# 32-041.net
KiCad netlist of a schematic drawn in Altium Designer
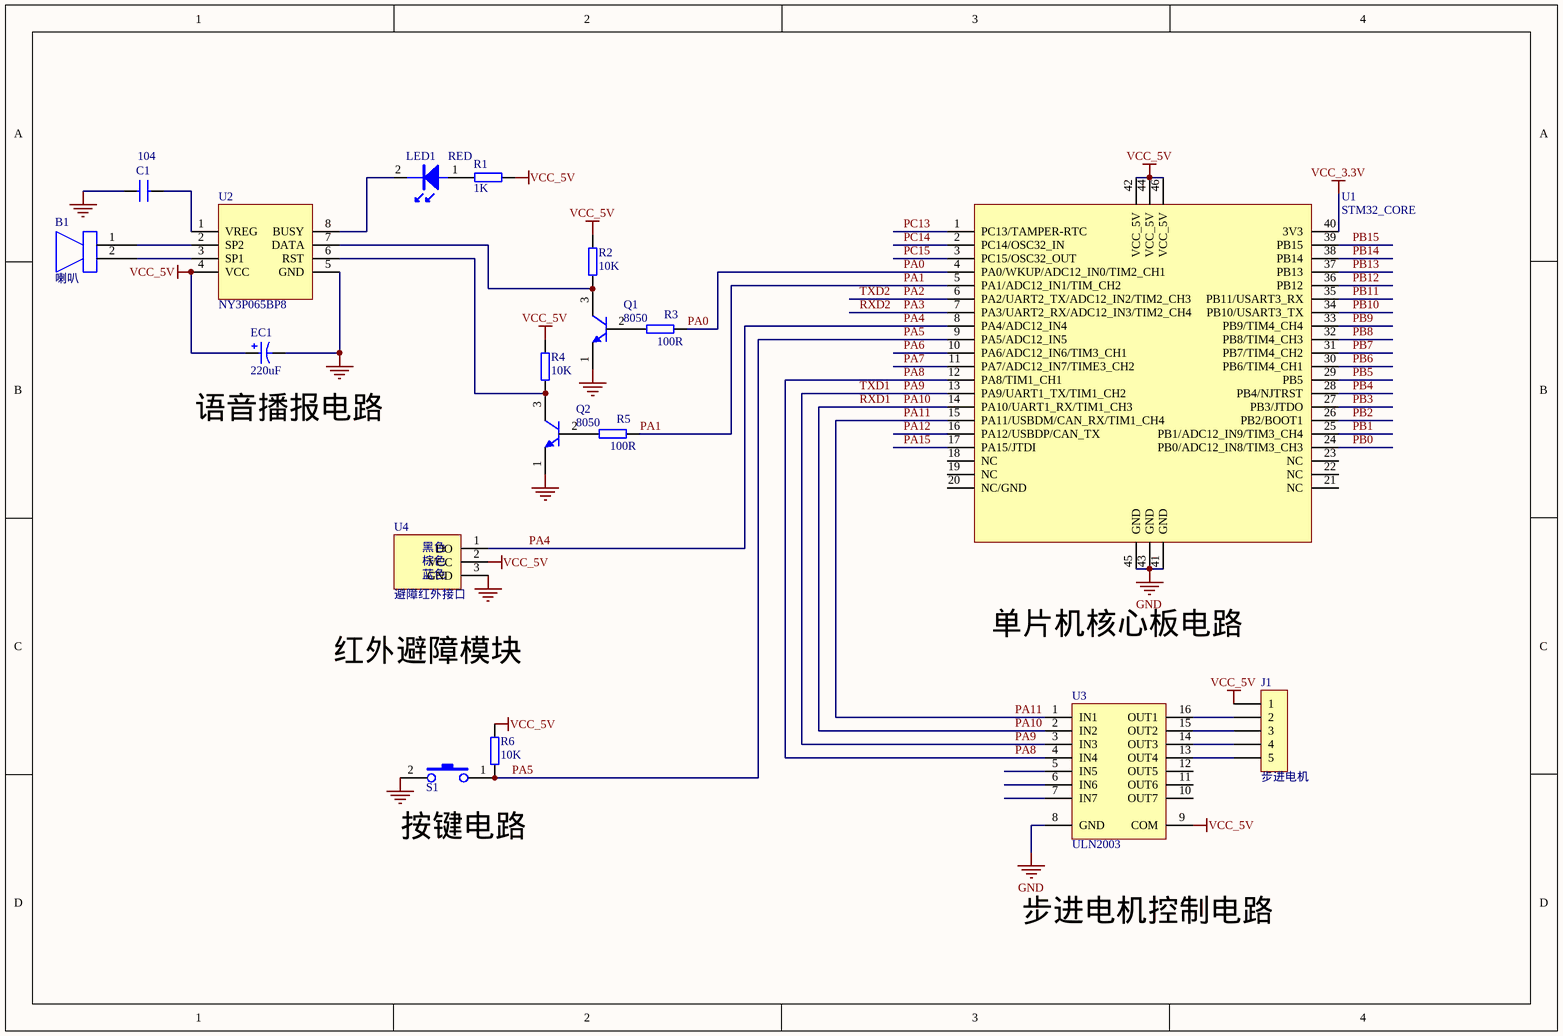
[diagram p0: 32-041原理图（源文件格式）.SchDoc]

(export (version "E")
  (design (tool "Eeschema 10.0.6"))
  (components
    (comp (ref "B1") (value "喇叭") (footprint "喇叭") (libsource (lib "参考") (part "喇叭")))
    (comp (ref "C1")
      (value "104")
      (footprint "RAD-0.1")
      (description "无极性电容")
      (libsource (lib "参考") (part "CAP"))
    )
    (comp (ref "EC1")
      (value "220uF")
      (footprint "RB.15/.3")
      (description "极性电容")
      (libsource (lib "参考") (part "CAP_EC"))
    )
    (comp (ref "J1")
      (value "步进电机")
      (footprint "SIP5-2.54")
      (description "步进电机接口")
      (libsource (lib "参考") (part "步进电机"))
    )
    (comp (ref "LED1")
      (value "RED")
      (footprint "LED_D3MM12")
      (description "LED灯")
      (libsource (lib "参考") (part "LED12"))
    )
    (comp (ref "Q1")
      (value "8050")
      (footprint "TO-92")
      (description "三极管")
      (libsource (lib "参考") (part "9013"))
    )
    (comp (ref "Q2")
      (value "8050")
      (footprint "TO-92")
      (description "三极管")
      (libsource (lib "参考") (part "9013"))
    )
    (comp (ref "R1")
      (value "1K")
      (footprint "AXIAL0.3")
      (description "电阻")
      (libsource (lib "参考") (part "RES"))
    )
    (comp (ref "R2")
      (value "10K")
      (footprint "AXIAL0.3")
      (description "电阻")
      (libsource (lib "参考") (part "RES"))
    )
    (comp (ref "R3")
      (value "100R")
      (footprint "AXIAL0.3")
      (description "电阻")
      (libsource (lib "参考") (part "RES"))
    )
    (comp (ref "R4")
      (value "10K")
      (footprint "AXIAL0.3")
      (description "电阻")
      (libsource (lib "参考") (part "RES"))
    )
    (comp (ref "R5")
      (value "100R")
      (footprint "AXIAL0.3")
      (description "电阻")
      (libsource (lib "参考") (part "RES"))
    )
    (comp (ref "R6")
      (value "10K")
      (footprint "AXIAL0.3")
      (description "电阻")
      (libsource (lib "参考") (part "RES"))
    )
    (comp (ref "S1")
      (value "BUTTOM")
      (footprint "BUTTOM_6x6DIP")
      (description "按键")
      (libsource (lib "参考") (part "BUTTOM"))
    )
    (comp (ref "U1")
      (value "STM32_CORE")
      (footprint "STM32_CORE")
      (description "STM32核心板")
      (libsource (lib "参考") (part "STM32_CORE"))
    )
    (comp (ref "U2")
      (value "NY3P065BP8")
      (footprint "DIP8")
      (description "语音芯片")
      (libsource (lib "参考") (part "NY3P065BP8"))
    )
    (comp (ref "U3")
      (value "ULN2003")
      (footprint "DIP16")
      (description "ULN2003芯片")
      (libsource (lib "参考") (part "ULN2003A"))
    )
    (comp (ref "U4")
      (value "避障红外接口")
      (footprint "红外接口")
      (description "避障红外探头模块")
      (libsource (lib "参考") (part "避障红外接口"))
    )
  )
  (nets
    (net (code "1") (name "/PA0") (class "Default")
      (node (ref "R3") (pin "1") (pinfunction "1_1") (pintype "passive"))
      (node (ref "U1") (pin "4") (pinfunction "PA0/WKUP/ADC12_IN0/TIM2_CH1_4") (pintype "passive"))
    )
    (net (code "2") (name "/PA1") (class "Default")
      (node (ref "R5") (pin "1") (pinfunction "1_1") (pintype "passive"))
      (node (ref "U1") (pin "5") (pinfunction "PA1/ADC12_IN1/TIM_CH2_5") (pintype "passive"))
    )
    (net (code "3") (name "/PA2") (class "Default")
      (node (ref "U1") (pin "6") (pinfunction "PA2/UART2_TX/ADC12_IN2/TIM2_CH3_6") (pintype "passive"))
    )
    (net (code "4") (name "/PA3") (class "Default")
      (node (ref "U1") (pin "7") (pinfunction "PA3/UART2_RX/ADC12_IN3/TIM2_CH4_7") (pintype "passive"))
    )
    (net (code "5") (name "/PA4") (class "Default")
      (node (ref "U1") (pin "8") (pinfunction "PA4/ADC12_IN4_8") (pintype "passive"))
      (node (ref "U4") (pin "1") (pinfunction "DO_1") (pintype "passive"))
    )
    (net (code "6") (name "/PA5") (class "Default")
      (node (ref "R6") (pin "1") (pinfunction "1_1") (pintype "passive"))
      (node (ref "S1") (pin "1") (pinfunction "1_1") (pintype "passive"))
      (node (ref "U1") (pin "9") (pinfunction "PA5/ADC12_IN5_9") (pintype "passive"))
    )
    (net (code "7") (name "/PA6") (class "Default")
      (node (ref "U1") (pin "10") (pinfunction "PA6/ADC12_IN6/TIM3_CH1_10") (pintype "passive"))
    )
    (net (code "8") (name "/PA7") (class "Default")
      (node (ref "U1") (pin "11") (pinfunction "PA7/ADC12_IN7/TIME3_CH2_11") (pintype "passive"))
    )
    (net (code "9") (name "/PA8") (class "Default")
      (node (ref "U1") (pin "12") (pinfunction "PA8/TIM1_CH1_12") (pintype "passive"))
      (node (ref "U3") (pin "4") (pinfunction "IN4_4") (pintype "passive"))
    )
    (net (code "10") (name "/PA9") (class "Default")
      (node (ref "U1") (pin "13") (pinfunction "PA9/UART1_TX/TIM1_CH2_13") (pintype "passive"))
      (node (ref "U3") (pin "3") (pinfunction "IN3_3") (pintype "passive"))
    )
    (net (code "11") (name "/PA10") (class "Default")
      (node (ref "U1") (pin "14") (pinfunction "PA10/UART1_RX/TIM1_CH3_14") (pintype "passive"))
      (node (ref "U3") (pin "2") (pinfunction "IN2_2") (pintype "passive"))
    )
    (net (code "12") (name "/PA11") (class "Default")
      (node (ref "U1") (pin "15") (pinfunction "PA11/USBDM/CAN_RX/TIM1_CH4_15") (pintype "passive"))
      (node (ref "U3") (pin "1") (pinfunction "IN1_1") (pintype "passive"))
    )
    (net (code "13") (name "/PA12") (class "Default")
      (node (ref "U1") (pin "16") (pinfunction "PA12/USBDP/CAN_TX_16") (pintype "passive"))
    )
    (net (code "14") (name "/PA15") (class "Default")
      (node (ref "U1") (pin "17") (pinfunction "PA15/JTDI_17") (pintype "passive"))
    )
    (net (code "15") (name "/PB0") (class "Default")
      (node (ref "U1") (pin "24") (pinfunction "PB0/ADC12_IN8/TIM3_CH3_24") (pintype "passive"))
    )
    (net (code "16") (name "/PB1") (class "Default")
      (node (ref "U1") (pin "25") (pinfunction "PB1/ADC12_IN9/TIM3_CH4_25") (pintype "passive"))
    )
    (net (code "17") (name "/PB2") (class "Default")
      (node (ref "U1") (pin "26") (pinfunction "PB2/BOOT1_26") (pintype "passive"))
    )
    (net (code "18") (name "/PB3") (class "Default")
      (node (ref "U1") (pin "27") (pinfunction "PB3/JTDO_27") (pintype "passive"))
    )
    (net (code "19") (name "/PB4") (class "Default")
      (node (ref "U1") (pin "28") (pinfunction "PB4/NJTRST_28") (pintype "passive"))
    )
    (net (code "20") (name "/PB5") (class "Default")
      (node (ref "U1") (pin "29") (pinfunction "PB5_29") (pintype "passive"))
    )
    (net (code "21") (name "/PB6") (class "Default")
      (node (ref "U1") (pin "30") (pinfunction "PB6/TIM4_CH1_30") (pintype "passive"))
    )
    (net (code "22") (name "/PB7") (class "Default")
      (node (ref "U1") (pin "31") (pinfunction "PB7/TIM4_CH2_31") (pintype "passive"))
    )
    (net (code "23") (name "/PB8") (class "Default")
      (node (ref "U1") (pin "32") (pinfunction "PB8/TIM4_CH3_32") (pintype "passive"))
    )
    (net (code "24") (name "/PB9") (class "Default")
      (node (ref "U1") (pin "33") (pinfunction "PB9/TIM4_CH4_33") (pintype "passive"))
    )
    (net (code "25") (name "/PB10") (class "Default")
      (node (ref "U1") (pin "34") (pinfunction "PB10/USART3_TX_34") (pintype "passive"))
    )
    (net (code "26") (name "/PB11") (class "Default")
      (node (ref "U1") (pin "35") (pinfunction "PB11/USART3_RX_35") (pintype "passive"))
    )
    (net (code "27") (name "/PB12") (class "Default")
      (node (ref "U1") (pin "36") (pinfunction "PB12_36") (pintype "passive"))
    )
    (net (code "28") (name "/PB13") (class "Default")
      (node (ref "U1") (pin "37") (pinfunction "PB13_37") (pintype "passive"))
    )
    (net (code "29") (name "/PB14") (class "Default")
      (node (ref "U1") (pin "38") (pinfunction "PB14_38") (pintype "passive"))
    )
    (net (code "30") (name "/PB15") (class "Default")
      (node (ref "U1") (pin "39") (pinfunction "PB15_39") (pintype "passive"))
    )
    (net (code "31") (name "/PC13") (class "Default")
      (node (ref "U1") (pin "1") (pinfunction "PC13/TAMPER-RTC_1") (pintype "passive"))
    )
    (net (code "32") (name "/PC14") (class "Default")
      (node (ref "U1") (pin "2") (pinfunction "PC14/OSC32_IN_2") (pintype "passive"))
    )
    (net (code "33") (name "/PC15") (class "Default")
      (node (ref "U1") (pin "3") (pinfunction "PC15/OSC32_OUT_3") (pintype "passive"))
    )
    (net (code "34") (name "GND") (class "Default")
      (node (ref "C1") (pin "1") (pinfunction "1_1") (pintype "passive"))
      (node (ref "EC1") (pin "2") (pinfunction "2_2") (pintype "passive"))
      (node (ref "Q1") (pin "1") (pinfunction "1_1") (pintype "passive"))
      (node (ref "Q2") (pin "1") (pinfunction "1_1") (pintype "passive"))
      (node (ref "S1") (pin "2") (pinfunction "2_2") (pintype "passive"))
      (node (ref "U1") (pin "41") (pinfunction "GND_41") (pintype "passive"))
      (node (ref "U1") (pin "43") (pinfunction "GND_43") (pintype "passive"))
      (node (ref "U1") (pin "45") (pinfunction "GND_45") (pintype "passive"))
      (node (ref "U2") (pin "5") (pinfunction "GND_5") (pintype "passive"))
      (node (ref "U3") (pin "8") (pinfunction "GND_8") (pintype "passive"))
      (node (ref "U4") (pin "3") (pinfunction "GND_3") (pintype "passive"))
    )
    (net (code "35") (name "Net-(B1-+)") (class "Default")
      (node (ref "B1") (pin "1") (pinfunction "+_1") (pintype "passive"))
      (node (ref "U2") (pin "2") (pinfunction "SP2_2") (pintype "passive"))
    )
    (net (code "36") (name "Net-(LED1-Pad1)") (class "Default")
      (node (ref "LED1") (pin "1") (pinfunction "1_1") (pintype "passive"))
      (node (ref "R1") (pin "1") (pinfunction "1_1") (pintype "passive"))
    )
    (net (code "37") (name "Net-(Q1-Pad2)") (class "Default")
      (node (ref "Q1") (pin "2") (pinfunction "2_2") (pintype "passive"))
      (node (ref "R3") (pin "2") (pinfunction "2_2") (pintype "passive"))
    )
    (net (code "38") (name "Net-(Q2-Pad2)") (class "Default")
      (node (ref "Q2") (pin "2") (pinfunction "2_2") (pintype "passive"))
      (node (ref "R5") (pin "2") (pinfunction "2_2") (pintype "passive"))
    )
    (net (code "39") (name "Net-(U2-BUSY)") (class "Default")
      (node (ref "LED1") (pin "2") (pinfunction "2_2") (pintype "passive"))
      (node (ref "U2") (pin "8") (pinfunction "BUSY_8") (pintype "passive"))
    )
    (net (code "40") (name "Net-(U2-DATA)") (class "Default")
      (node (ref "Q1") (pin "3") (pinfunction "3_3") (pintype "passive"))
      (node (ref "R2") (pin "1") (pinfunction "1_1") (pintype "passive"))
      (node (ref "U2") (pin "7") (pinfunction "DATA_7") (pintype "passive"))
    )
    (net (code "41") (name "Net-(U2-RST)") (class "Default")
      (node (ref "Q2") (pin "3") (pinfunction "3_3") (pintype "passive"))
      (node (ref "R4") (pin "1") (pinfunction "1_1") (pintype "passive"))
      (node (ref "U2") (pin "6") (pinfunction "RST_6") (pintype "passive"))
    )
    (net (code "42") (name "Net-(U2-SP1)") (class "Default")
      (node (ref "B1") (pin "2") (pintype "passive"))
      (node (ref "U2") (pin "3") (pinfunction "SP1_3") (pintype "passive"))
    )
    (net (code "43") (name "Net-(U2-VREG)") (class "Default")
      (node (ref "C1") (pin "2") (pinfunction "2_2") (pintype "passive"))
      (node (ref "U2") (pin "1") (pinfunction "VREG_1") (pintype "passive"))
    )
    (net (code "44") (name "Net-(U3-OUT1)") (class "Default")
      (node (ref "J1") (pin "2") (pinfunction "2_2") (pintype "passive"))
      (node (ref "U3") (pin "16") (pinfunction "OUT1_16") (pintype "passive"))
    )
    (net (code "45") (name "Net-(U3-OUT2)") (class "Default")
      (node (ref "J1") (pin "3") (pinfunction "3_3") (pintype "passive"))
      (node (ref "U3") (pin "15") (pinfunction "OUT2_15") (pintype "passive"))
    )
    (net (code "46") (name "Net-(U3-OUT3)") (class "Default")
      (node (ref "J1") (pin "4") (pinfunction "4_4") (pintype "passive"))
      (node (ref "U3") (pin "14") (pinfunction "OUT3_14") (pintype "passive"))
    )
    (net (code "47") (name "Net-(U3-OUT4)") (class "Default")
      (node (ref "J1") (pin "5") (pinfunction "5_5") (pintype "passive"))
      (node (ref "U3") (pin "13") (pinfunction "OUT4_13") (pintype "passive"))
    )
    (net (code "48") (name "VCC_3.3V") (class "Default")
      (node (ref "U1") (pin "40") (pinfunction "3V3_40") (pintype "passive"))
    )
    (net (code "49") (name "VCC_5V") (class "Default")
      (node (ref "EC1") (pin "1") (pinfunction "1_1") (pintype "passive"))
      (node (ref "J1") (pin "1") (pinfunction "1_1") (pintype "passive"))
      (node (ref "R1") (pin "2") (pinfunction "2_2") (pintype "passive"))
      (node (ref "R2") (pin "2") (pinfunction "2_2") (pintype "passive"))
      (node (ref "R4") (pin "2") (pinfunction "2_2") (pintype "passive"))
      (node (ref "R6") (pin "2") (pinfunction "2_2") (pintype "passive"))
      (node (ref "U1") (pin "42") (pinfunction "VCC_5V_42") (pintype "passive"))
      (node (ref "U1") (pin "44") (pinfunction "VCC_5V_44") (pintype "passive"))
      (node (ref "U1") (pin "46") (pinfunction "VCC_5V_46") (pintype "passive"))
      (node (ref "U2") (pin "4") (pinfunction "VCC_4") (pintype "passive"))
      (node (ref "U3") (pin "9") (pinfunction "COM_9") (pintype "passive"))
      (node (ref "U4") (pin "2") (pinfunction "VCC_2") (pintype "passive"))
    )
    (net (code "50") (name "unconnected-(U1-NC-Pad18)") (class "Default")
      (node (ref "U1") (pin "18") (pinfunction "NC_18") (pintype "passive"))
    )
    (net (code "51") (name "unconnected-(U1-NC-Pad19)") (class "Default")
      (node (ref "U1") (pin "19") (pinfunction "NC_19") (pintype "passive"))
    )
    (net (code "52") (name "unconnected-(U1-NC-Pad21)") (class "Default")
      (node (ref "U1") (pin "21") (pinfunction "NC_21") (pintype "passive"))
    )
    (net (code "53") (name "unconnected-(U1-NC-Pad22)") (class "Default")
      (node (ref "U1") (pin "22") (pinfunction "NC_22") (pintype "passive"))
    )
    (net (code "54") (name "unconnected-(U1-NC-Pad23)") (class "Default")
      (node (ref "U1") (pin "23") (pinfunction "NC_23") (pintype "passive"))
    )
    (net (code "55") (name "unconnected-(U1-NC{slash}GND-Pad20)") (class "Default")
      (node (ref "U1") (pin "20") (pinfunction "NC/GND_20") (pintype "passive"))
    )
    (net (code "56") (name "unconnected-(U3-IN5-Pad5)") (class "Default")
      (node (ref "U3") (pin "5") (pinfunction "IN5_5") (pintype "passive"))
    )
    (net (code "57") (name "unconnected-(U3-IN6-Pad6)") (class "Default")
      (node (ref "U3") (pin "6") (pinfunction "IN6_6") (pintype "passive"))
    )
    (net (code "58") (name "unconnected-(U3-IN7-Pad7)") (class "Default")
      (node (ref "U3") (pin "7") (pinfunction "IN7_7") (pintype "passive"))
    )
    (net (code "59") (name "unconnected-(U3-OUT5-Pad12)") (class "Default")
      (node (ref "U3") (pin "12") (pinfunction "OUT5_12") (pintype "passive"))
    )
    (net (code "60") (name "unconnected-(U3-OUT6-Pad11)") (class "Default")
      (node (ref "U3") (pin "11") (pinfunction "OUT6_11") (pintype "passive"))
    )
    (net (code "61") (name "unconnected-(U3-OUT7-Pad10)") (class "Default")
      (node (ref "U3") (pin "10") (pinfunction "OUT7_10") (pintype "passive"))
    )
  )
)
